# StepCounter_sensor.net
KiCad netlist of a schematic drawn in Altium Designer
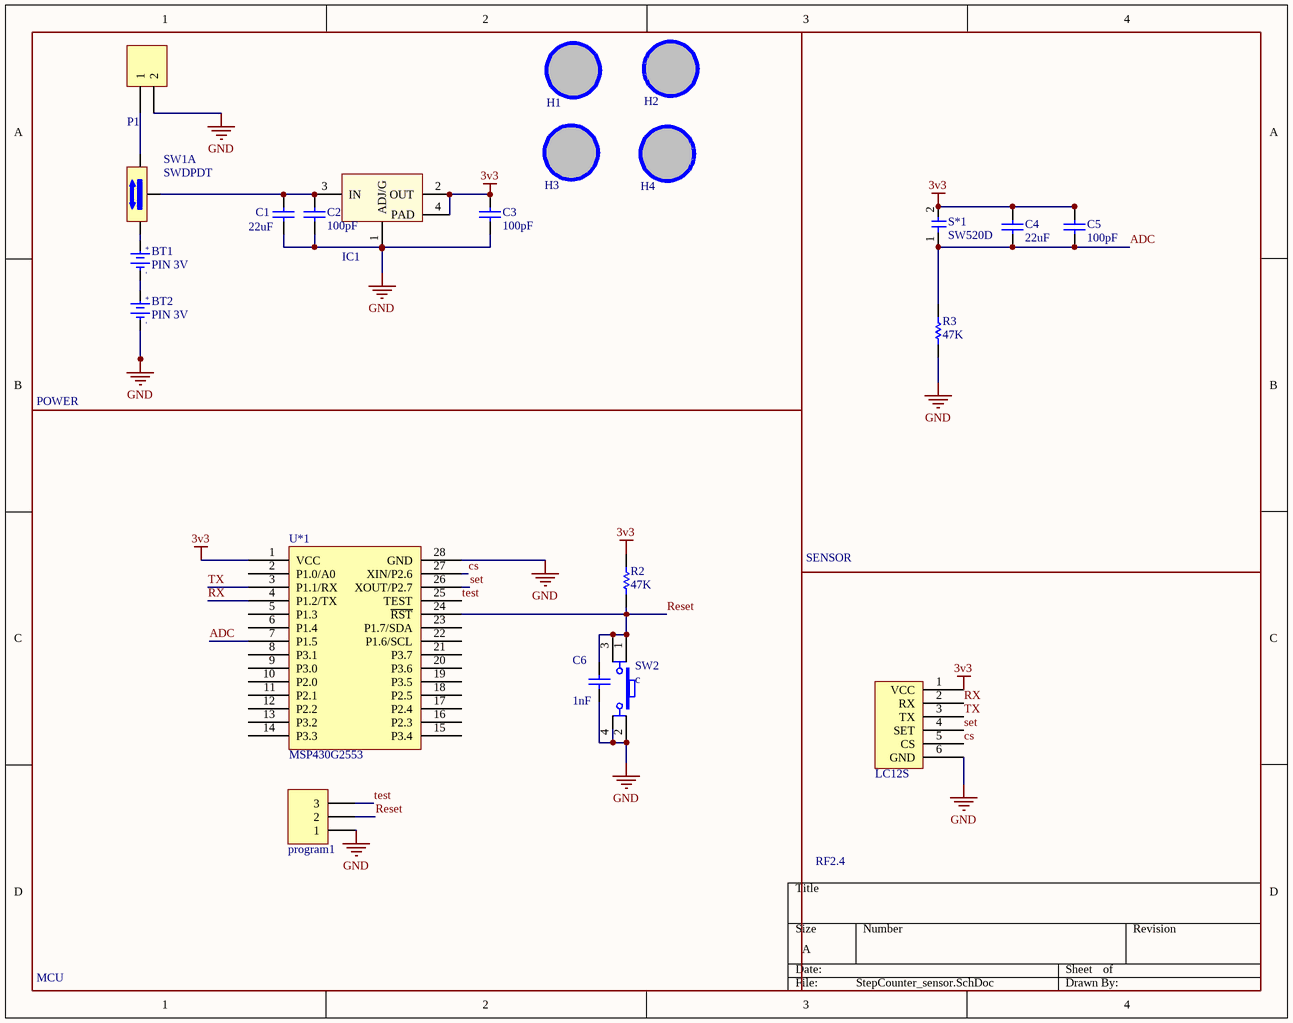
[diagram p0: StepCounter_sensor.SchDoc]

(export (version "E")
  (design (tool "Eeschema 10.0.6"))
  (components
    (comp (ref "BT1")
      (value "PIN 3V")
      (footprint "PIN3V")
      (description "Battery 3VDC")
      (libsource (lib "syhaunguyen") (part "PIN 3V"))
    )
    (comp (ref "BT2")
      (value "PIN 3V")
      (footprint "PIN3V")
      (description "Battery 3VDC")
      (libsource (lib "syhaunguyen") (part "PIN 3V"))
    )
    (comp (ref "C1")
      (value "22uF")
      (footprint "CAP-SM-0805")
      (description "Capacitor")
      (fields (field (name "Comment") "Cap Non-Pol SMD"))
      (libsource (lib "PIF_Schematic_Lib") (part "Cap Non-Pol SMD"))
    )
    (comp (ref "C2")
      (value "100pF")
      (footprint "CAP-SM-0805")
      (description "Capacitor")
      (fields (field (name "Comment") "Cap Non-Pol SMD"))
      (libsource (lib "PIF_Schematic_Lib") (part "Cap Non-Pol SMD"))
    )
    (comp (ref "C3")
      (value "100pF")
      (footprint "CAP-SM-0805")
      (description "Capacitor")
      (fields (field (name "Comment") "Cap Non-Pol SMD"))
      (libsource (lib "PIF_Schematic_Lib") (part "Cap Non-Pol SMD"))
    )
    (comp (ref "C4")
      (value "22uF")
      (footprint "CAP-SM-0603")
      (description "Capacitor")
      (fields (field (name "Comment") "Cap Non-Pol SMD"))
      (libsource (lib "PIF_Schematic_Lib") (part "Cap Non-Pol SMD"))
    )
    (comp (ref "C5")
      (value "100pF")
      (footprint "CAP-SM-0603")
      (description "Capacitor")
      (fields (field (name "Comment") "Cap Non-Pol SMD"))
      (libsource (lib "PIF_Schematic_Lib") (part "Cap Non-Pol SMD"))
    )
    (comp (ref "C6")
      (value "1nF")
      (footprint "CAP-SM-0603")
      (description "Capacitor")
      (fields (field (name "Comment") "Cap Non-Pol SMD"))
      (libsource (lib "PIF_Schematic_Lib - Copy") (part "Cap Non-Pol SMD"))
    )
    (comp (ref "H1")
      (value "Hole")
      (footprint "LO KHOAN 3MM")
      (description "Hole 3mm")
      (libsource (lib "PIF_Schematic_Lib") (part "Hole"))
    )
    (comp (ref "H2")
      (value "Hole")
      (footprint "LO KHOAN 3MM")
      (description "Hole 3mm")
      (libsource (lib "PIF_Schematic_Lib") (part "Hole"))
    )
    (comp (ref "H3")
      (value "Hole")
      (footprint "LO KHOAN 3MM")
      (description "Hole 3mm")
      (libsource (lib "PIF_Schematic_Lib") (part "Hole"))
    )
    (comp (ref "H4")
      (value "Hole")
      (footprint "LO KHOAN 3MM")
      (description "Hole 3mm")
      (libsource (lib "PIF_Schematic_Lib") (part "Hole"))
    )
    (comp (ref "IC1")
      (value "LM1117")
      (footprint "SOT223-4N")
      (description "Available in 1.8V, 2.5V, 2.85V, 3.3V, 5V, and  Adjustable Versions")
      (libsource (lib "PIF_Schematic_Lib") (part "LM1117"))
    )
    (comp (ref "P1")
      (value "Header 2")
      (footprint "JP2")
      (description "Header, 2-Pin")
      (fields (field (name "PUBLISHER") "Altium Limited"))
      (libsource (lib "PIF_Schematic_Lib") (part "Header 2"))
    )
    (comp (ref "program1")
      (value "Header 3")
      (footprint "JP3")
      (description "Header, 3-Pin")
      (fields (field (name "PUBLISHER") "Altium Limited"))
      (libsource (lib "PIF_Schematic_Lib - Copy") (part "Header 3"))
    )
    (comp (ref "R2")
      (value "47K")
      (footprint "RES-SM-0603")
      (description "Resistor")
      (fields (field (name "Comment") "RESISTOR SMD"))
      (libsource (lib "PIF_Schematic_Lib - Copy") (part "RESISTOR SMD"))
    )
    (comp (ref "R3")
      (value "47K")
      (footprint "RES-SM-0603")
      (description "Resistor")
      (fields (field (name "Comment") "RESISTOR SMD"))
      (libsource (lib "PIF_Schematic_Lib") (part "RESISTOR SMD"))
    )
    (comp (ref "RF*1")
      (value "LC12S")
      (footprint "StepCounter_sensor_pcblib:JP6")
      (libsource (lib "StepCounter_sensor_schlib") (part "LC12S"))
    )
    (comp (ref "S*1")
      (value "SW520D")
      (footprint "CP1/2")
      (libsource (lib "StepCounter_sensor_schlib") (part "SW520D"))
    )
    (comp (ref "SW1")
      (value "SWDPDT")
      (footprint "SWDPDT_1.5x1")
      (description "Switch SPDT")
      (fields (field (name "CREAT BY") "VanDungEvn@Gmail.com"))
      (libsource (lib "syhaunguyen") (part "SWDPDT"))
    )
    (comp (ref "SW2")
      (value "c")
      (footprint "SW4")
      (description "Switch button 4 pin")
      (libsource (lib "syhaunguyen") (part "SW4"))
    )
    (comp (ref "U*1")
      (value "MSP430G2553")
      (footprint "StepCounter_sensor_pcblib:msp430g2553tsstop")
      (libsource (lib "StepCounter_sensor_schlib") (part "MSP430G2553"))
    )
  )
  (nets
    (net (code "1") (name "/ADC") (class "Default")
      (node (ref "C4") (pin "1") (pinfunction "1_1") (pintype "passive"))
      (node (ref "C5") (pin "1") (pinfunction "1_1") (pintype "passive"))
      (node (ref "R3") (pin "2") (pinfunction "2_2") (pintype "passive"))
      (node (ref "S*1") (pin "1") (pinfunction "1_1") (pintype "passive"))
      (node (ref "U*1") (pin "7") (pinfunction "P1.5_7") (pintype "passive"))
    )
    (net (code "2") (name "/RX") (class "Default")
      (node (ref "RF*1") (pin "2") (pinfunction "RX_2") (pintype "passive"))
      (node (ref "U*1") (pin "4") (pinfunction "P1.2/TX_4") (pintype "passive"))
    )
    (net (code "3") (name "/Reset") (class "Default")
      (node (ref "C6") (pin "1") (pinfunction "1_1") (pintype "passive"))
      (node (ref "R2") (pin "2") (pinfunction "2_2") (pintype "passive"))
      (node (ref "SW2") (pin "1") (pintype "passive"))
      (node (ref "SW2") (pin "3") (pintype "passive"))
      (node (ref "U*1") (pin "24") (pinfunction "~{RST}_24") (pintype "passive"))
      (node (ref "program1") (pin "2") (pinfunction "2_2") (pintype "passive"))
    )
    (net (code "4") (name "/TX") (class "Default")
      (node (ref "RF*1") (pin "3") (pinfunction "TX_3") (pintype "passive"))
      (node (ref "U*1") (pin "3") (pinfunction "P1.1/RX_3") (pintype "passive"))
    )
    (net (code "5") (name "/cs") (class "Default")
      (node (ref "RF*1") (pin "5") (pinfunction "CS_5") (pintype "passive"))
      (node (ref "U*1") (pin "27") (pinfunction "XIN/P2.6_27") (pintype "passive"))
    )
    (net (code "6") (name "/set") (class "Default")
      (node (ref "RF*1") (pin "4") (pinfunction "SET_4") (pintype "passive"))
      (node (ref "U*1") (pin "26") (pinfunction "XOUT/P2.7_26") (pintype "passive"))
    )
    (net (code "7") (name "/test") (class "Default")
      (node (ref "U*1") (pin "25") (pinfunction "TEST_25") (pintype "passive"))
      (node (ref "program1") (pin "3") (pinfunction "3_3") (pintype "passive"))
    )
    (net (code "8") (name "3v3") (class "Default")
      (node (ref "C3") (pin "1") (pinfunction "1_1") (pintype "passive"))
      (node (ref "C4") (pin "2") (pinfunction "2_2") (pintype "passive"))
      (node (ref "C5") (pin "2") (pinfunction "2_2") (pintype "passive"))
      (node (ref "IC1") (pin "2") (pinfunction "OUT_2") (pintype "passive"))
      (node (ref "IC1") (pin "4") (pinfunction "PAD_4") (pintype "passive"))
      (node (ref "R2") (pin "1") (pinfunction "1_1") (pintype "passive"))
      (node (ref "RF*1") (pin "1") (pinfunction "VCC_1") (pintype "passive"))
      (node (ref "S*1") (pin "2") (pinfunction "2_2") (pintype "passive"))
      (node (ref "U*1") (pin "1") (pinfunction "VCC_1") (pintype "passive"))
    )
    (net (code "9") (name "GND") (class "Default")
      (node (ref "BT2") (pin "2") (pinfunction "GND_2") (pintype "passive"))
      (node (ref "C1") (pin "1") (pinfunction "1_1") (pintype "passive"))
      (node (ref "C2") (pin "1") (pinfunction "1_1") (pintype "passive"))
      (node (ref "C3") (pin "2") (pinfunction "2_2") (pintype "passive"))
      (node (ref "C6") (pin "2") (pinfunction "2_2") (pintype "passive"))
      (node (ref "IC1") (pin "1") (pinfunction "ADJ/G_1") (pintype "passive"))
      (node (ref "P1") (pin "2") (pinfunction "2_2") (pintype "passive"))
      (node (ref "R3") (pin "1") (pinfunction "1_1") (pintype "passive"))
      (node (ref "RF*1") (pin "6") (pinfunction "GND_6") (pintype "passive"))
      (node (ref "SW2") (pin "2") (pintype "passive"))
      (node (ref "SW2") (pin "4") (pintype "passive"))
      (node (ref "U*1") (pin "28") (pinfunction "GND_28") (pintype "passive"))
      (node (ref "program1") (pin "1") (pinfunction "1_1") (pintype "passive"))
    )
    (net (code "10") (name "Net-(BT1-+3V)") (class "Default")
      (node (ref "BT1") (pin "1") (pinfunction "+3V_1") (pintype "passive"))
      (node (ref "SW1") (pin "1") (pinfunction "1_1") (pintype "passive"))
    )
    (net (code "11") (name "Net-(BT1-GND)") (class "Default")
      (node (ref "BT1") (pin "2") (pinfunction "GND_2") (pintype "passive"))
      (node (ref "BT2") (pin "1") (pinfunction "+3V_1") (pintype "passive"))
    )
    (net (code "12") (name "Net-(IC1-IN)") (class "Default")
      (node (ref "C1") (pin "2") (pinfunction "2_2") (pintype "passive"))
      (node (ref "C2") (pin "2") (pinfunction "2_2") (pintype "passive"))
      (node (ref "IC1") (pin "3") (pinfunction "IN_3") (pintype "passive"))
      (node (ref "SW1") (pin "2") (pinfunction "2_2") (pintype "passive"))
    )
    (net (code "13") (name "Net-(P1-Pad1)") (class "Default")
      (node (ref "P1") (pin "1") (pinfunction "1_1") (pintype "passive"))
      (node (ref "SW1") (pin "3") (pinfunction "3_3") (pintype "passive"))
    )
    (net (code "14") (name "unconnected-(H1-Pad1)") (class "Default")
      (node (ref "H1") (pin "1") (pinfunction "1_1") (pintype "passive"))
    )
    (net (code "15") (name "unconnected-(H2-Pad1)") (class "Default")
      (node (ref "H2") (pin "1") (pinfunction "1_1") (pintype "passive"))
    )
    (net (code "16") (name "unconnected-(H3-Pad1)") (class "Default")
      (node (ref "H3") (pin "1") (pinfunction "1_1") (pintype "passive"))
    )
    (net (code "17") (name "unconnected-(H4-Pad1)") (class "Default")
      (node (ref "H4") (pin "1") (pinfunction "1_1") (pintype "passive"))
    )
    (net (code "18") (name "unconnected-(U*1-P1.0{slash}A0-Pad2)") (class "Default")
      (node (ref "U*1") (pin "2") (pinfunction "P1.0/A0_2") (pintype "passive"))
    )
    (net (code "19") (name "unconnected-(U*1-P1.3-Pad5)") (class "Default")
      (node (ref "U*1") (pin "5") (pinfunction "P1.3_5") (pintype "passive"))
    )
    (net (code "20") (name "unconnected-(U*1-P1.4-Pad6)") (class "Default")
      (node (ref "U*1") (pin "6") (pinfunction "P1.4_6") (pintype "passive"))
    )
    (net (code "21") (name "unconnected-(U*1-P1.6{slash}SCL-Pad22)") (class "Default")
      (node (ref "U*1") (pin "22") (pinfunction "P1.6/SCL_22") (pintype "passive"))
    )
    (net (code "22") (name "unconnected-(U*1-P1.7{slash}SDA-Pad23)") (class "Default")
      (node (ref "U*1") (pin "23") (pinfunction "P1.7/SDA_23") (pintype "passive"))
    )
    (net (code "23") (name "unconnected-(U*1-P2.0-Pad10)") (class "Default")
      (node (ref "U*1") (pin "10") (pinfunction "P2.0_10") (pintype "passive"))
    )
    (net (code "24") (name "unconnected-(U*1-P2.1-Pad11)") (class "Default")
      (node (ref "U*1") (pin "11") (pinfunction "P2.1_11") (pintype "passive"))
    )
    (net (code "25") (name "unconnected-(U*1-P2.2-Pad12)") (class "Default")
      (node (ref "U*1") (pin "12") (pinfunction "P2.2_12") (pintype "passive"))
    )
    (net (code "26") (name "unconnected-(U*1-P2.3-Pad16)") (class "Default")
      (node (ref "U*1") (pin "16") (pinfunction "P2.3_16") (pintype "passive"))
    )
    (net (code "27") (name "unconnected-(U*1-P2.4-Pad17)") (class "Default")
      (node (ref "U*1") (pin "17") (pinfunction "P2.4_17") (pintype "passive"))
    )
    (net (code "28") (name "unconnected-(U*1-P2.5-Pad18)") (class "Default")
      (node (ref "U*1") (pin "18") (pinfunction "P2.5_18") (pintype "passive"))
    )
    (net (code "29") (name "unconnected-(U*1-P3.0-Pad9)") (class "Default")
      (node (ref "U*1") (pin "9") (pinfunction "P3.0_9") (pintype "passive"))
    )
    (net (code "30") (name "unconnected-(U*1-P3.1-Pad8)") (class "Default")
      (node (ref "U*1") (pin "8") (pinfunction "P3.1_8") (pintype "passive"))
    )
    (net (code "31") (name "unconnected-(U*1-P3.2-Pad13)") (class "Default")
      (node (ref "U*1") (pin "13") (pinfunction "P3.2_13") (pintype "passive"))
    )
    (net (code "32") (name "unconnected-(U*1-P3.3-Pad14)") (class "Default")
      (node (ref "U*1") (pin "14") (pinfunction "P3.3_14") (pintype "passive"))
    )
    (net (code "33") (name "unconnected-(U*1-P3.4-Pad15)") (class "Default")
      (node (ref "U*1") (pin "15") (pinfunction "P3.4_15") (pintype "passive"))
    )
    (net (code "34") (name "unconnected-(U*1-P3.5-Pad19)") (class "Default")
      (node (ref "U*1") (pin "19") (pinfunction "P3.5_19") (pintype "passive"))
    )
    (net (code "35") (name "unconnected-(U*1-P3.6-Pad20)") (class "Default")
      (node (ref "U*1") (pin "20") (pinfunction "P3.6_20") (pintype "passive"))
    )
    (net (code "36") (name "unconnected-(U*1-P3.7-Pad21)") (class "Default")
      (node (ref "U*1") (pin "21") (pinfunction "P3.7_21") (pintype "passive"))
    )
  )
)
